# Adafruit_MCP9808_Breakout.net
KiCad netlist of a schematic drawn in EAGLE
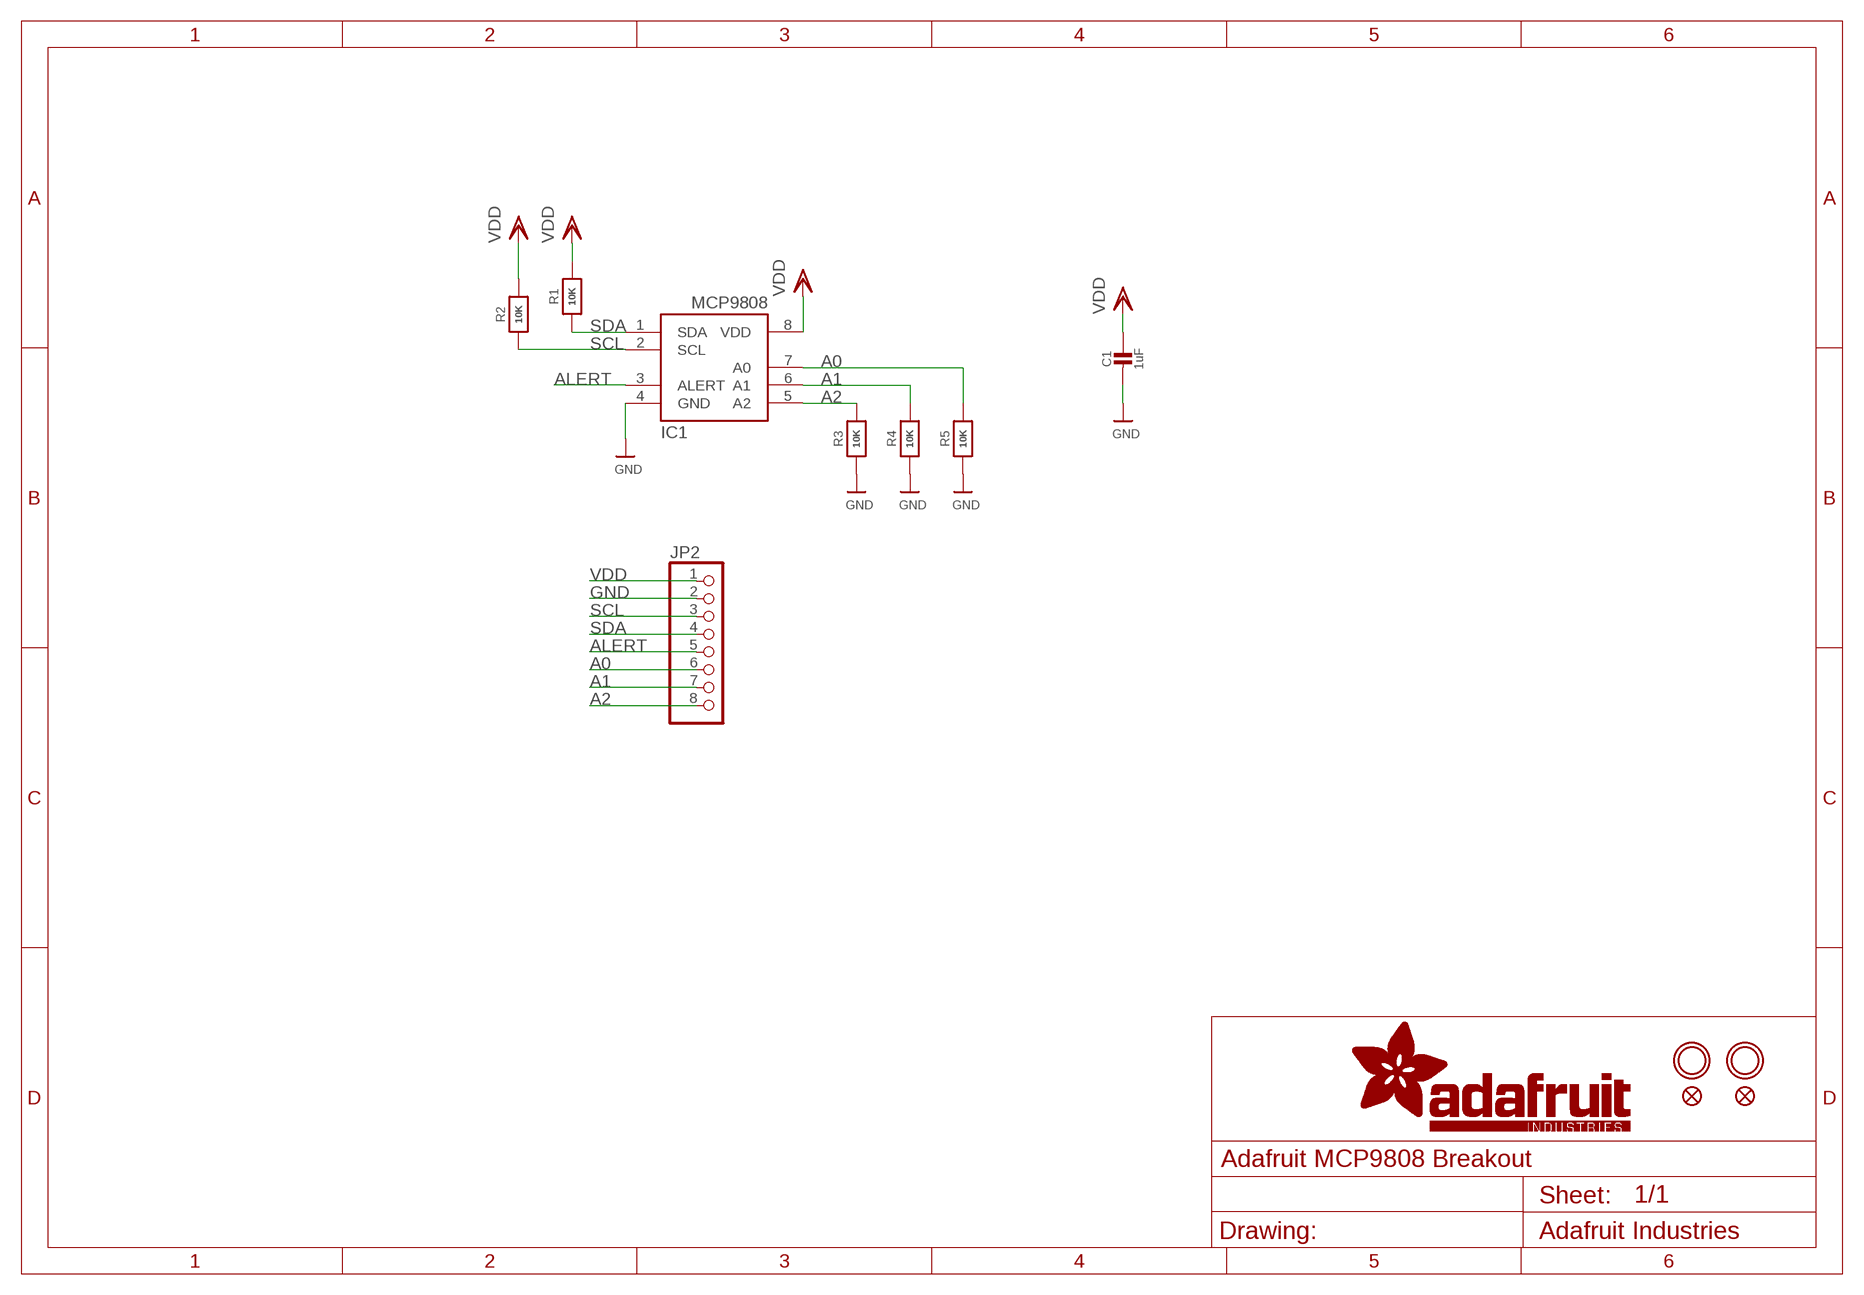
[diagram p0: schematic, sheet 1]

(export (version "E")
  (design (tool "Eeschema 10.0.6"))
  (components
    (comp (ref "C1")
      (value "1uF")
      (footprint "eagle-import:_0805MP")
      (libsource (lib "eagle-import") (part "CAP_CERAMIC_0805MP"))
    )
    (comp (ref "FID1")
      (value "FIDUCIAL\"\"")
      (footprint "eagle-import:FIDUCIAL_1MM")
      (libsource (lib "eagle-import") (part "FIDUCIAL{dblquote}{dblquote}"))
    )
    (comp (ref "FID2")
      (value "FIDUCIAL\"\"")
      (footprint "eagle-import:FIDUCIAL_1MM")
      (libsource (lib "eagle-import") (part "FIDUCIAL{dblquote}{dblquote}"))
    )
    (comp (ref "IC1")
      (value "MCP9808-E/MS")
      (footprint "eagle-import:MSOP8_0.65MM")
      (libsource (lib "eagle-import") (part "MCP9808-E/MS"))
    )
    (comp (ref "JP2")
      (value "HEADER-1X870MIL")
      (footprint "eagle-import:1X08_ROUND_70")
      (libsource (lib "eagle-import") (part "HEADER-1X870MIL"))
    )
    (comp (ref "R1")
      (value "10K")
      (footprint "eagle-import:0805-NO")
      (libsource (lib "eagle-import") (part "RESISTOR0805_NOOUTLINE"))
    )
    (comp (ref "R2")
      (value "10K")
      (footprint "eagle-import:0805-NO")
      (libsource (lib "eagle-import") (part "RESISTOR0805_NOOUTLINE"))
    )
    (comp (ref "R3")
      (value "10K")
      (footprint "eagle-import:0805-NO")
      (libsource (lib "eagle-import") (part "RESISTOR0805_NOOUTLINE"))
    )
    (comp (ref "R4")
      (value "10K")
      (footprint "eagle-import:0805-NO")
      (libsource (lib "eagle-import") (part "RESISTOR0805_NOOUTLINE"))
    )
    (comp (ref "R5")
      (value "10K")
      (footprint "eagle-import:0805-NO")
      (libsource (lib "eagle-import") (part "RESISTOR0805_NOOUTLINE"))
    )
    (comp (ref "U$3")
      (value "MOUNTINGHOLE2.5")
      (footprint "eagle-import:MOUNTINGHOLE_2.5_PLATED")
      (libsource (lib "eagle-import") (part "MOUNTINGHOLE2.5"))
    )
    (comp (ref "U$5")
      (value "MOUNTINGHOLE2.5")
      (footprint "eagle-import:MOUNTINGHOLE_2.5_PLATED")
      (libsource (lib "eagle-import") (part "MOUNTINGHOLE2.5"))
    )
  )
  (nets
    (net (code "1") (name "/A0") (class "Default")
      (node (ref "IC1") (pin "7") (pinfunction "A0_7") (pintype "input"))
      (node (ref "JP2") (pin "6") (pinfunction "6_6") (pintype "passive"))
      (node (ref "R5") (pin "2") (pinfunction "2_2") (pintype "passive"))
    )
    (net (code "2") (name "/A1") (class "Default")
      (node (ref "IC1") (pin "6") (pinfunction "A1_6") (pintype "input"))
      (node (ref "JP2") (pin "7") (pinfunction "7_7") (pintype "passive"))
      (node (ref "R4") (pin "2") (pinfunction "2_2") (pintype "passive"))
    )
    (net (code "3") (name "/A2") (class "Default")
      (node (ref "IC1") (pin "5") (pinfunction "A2_5") (pintype "input"))
      (node (ref "JP2") (pin "8") (pinfunction "8_8") (pintype "passive"))
      (node (ref "R3") (pin "2") (pinfunction "2_2") (pintype "passive"))
    )
    (net (code "4") (name "/ALERT") (class "Default")
      (node (ref "IC1") (pin "3") (pinfunction "ALERT_3") (pintype "open_collector"))
      (node (ref "JP2") (pin "5") (pinfunction "5_5") (pintype "passive"))
    )
    (net (code "5") (name "/SCL") (class "Default")
      (node (ref "IC1") (pin "2") (pinfunction "SCL_2") (pintype "bidirectional"))
      (node (ref "JP2") (pin "3") (pinfunction "3_3") (pintype "passive"))
      (node (ref "R2") (pin "1") (pinfunction "1_1") (pintype "passive"))
    )
    (net (code "6") (name "/SDA") (class "Default")
      (node (ref "IC1") (pin "1") (pinfunction "SDA_1") (pintype "bidirectional"))
      (node (ref "JP2") (pin "4") (pinfunction "4_4") (pintype "passive"))
      (node (ref "R1") (pin "1") (pinfunction "1_1") (pintype "passive"))
    )
    (net (code "7") (name "GND") (class "Default")
      (node (ref "C1") (pin "2") (pinfunction "2_2") (pintype "passive"))
      (node (ref "IC1") (pin "4") (pinfunction "GND_4") (pintype "power_in"))
      (node (ref "JP2") (pin "2") (pinfunction "2_2") (pintype "passive"))
      (node (ref "R3") (pin "1") (pinfunction "1_1") (pintype "passive"))
      (node (ref "R4") (pin "1") (pinfunction "1_1") (pintype "passive"))
      (node (ref "R5") (pin "1") (pinfunction "1_1") (pintype "passive"))
    )
    (net (code "8") (name "VDD") (class "Default")
      (node (ref "C1") (pin "1") (pinfunction "1_1") (pintype "passive"))
      (node (ref "IC1") (pin "8") (pinfunction "VDD_8") (pintype "power_in"))
      (node (ref "JP2") (pin "1") (pinfunction "1_1") (pintype "passive"))
      (node (ref "R1") (pin "2") (pinfunction "2_2") (pintype "passive"))
      (node (ref "R2") (pin "2") (pinfunction "2_2") (pintype "passive"))
    )
  )
)
